# EEM_Connectors_JTAG.net
KiCad netlist of a schematic drawn in Altium Designer
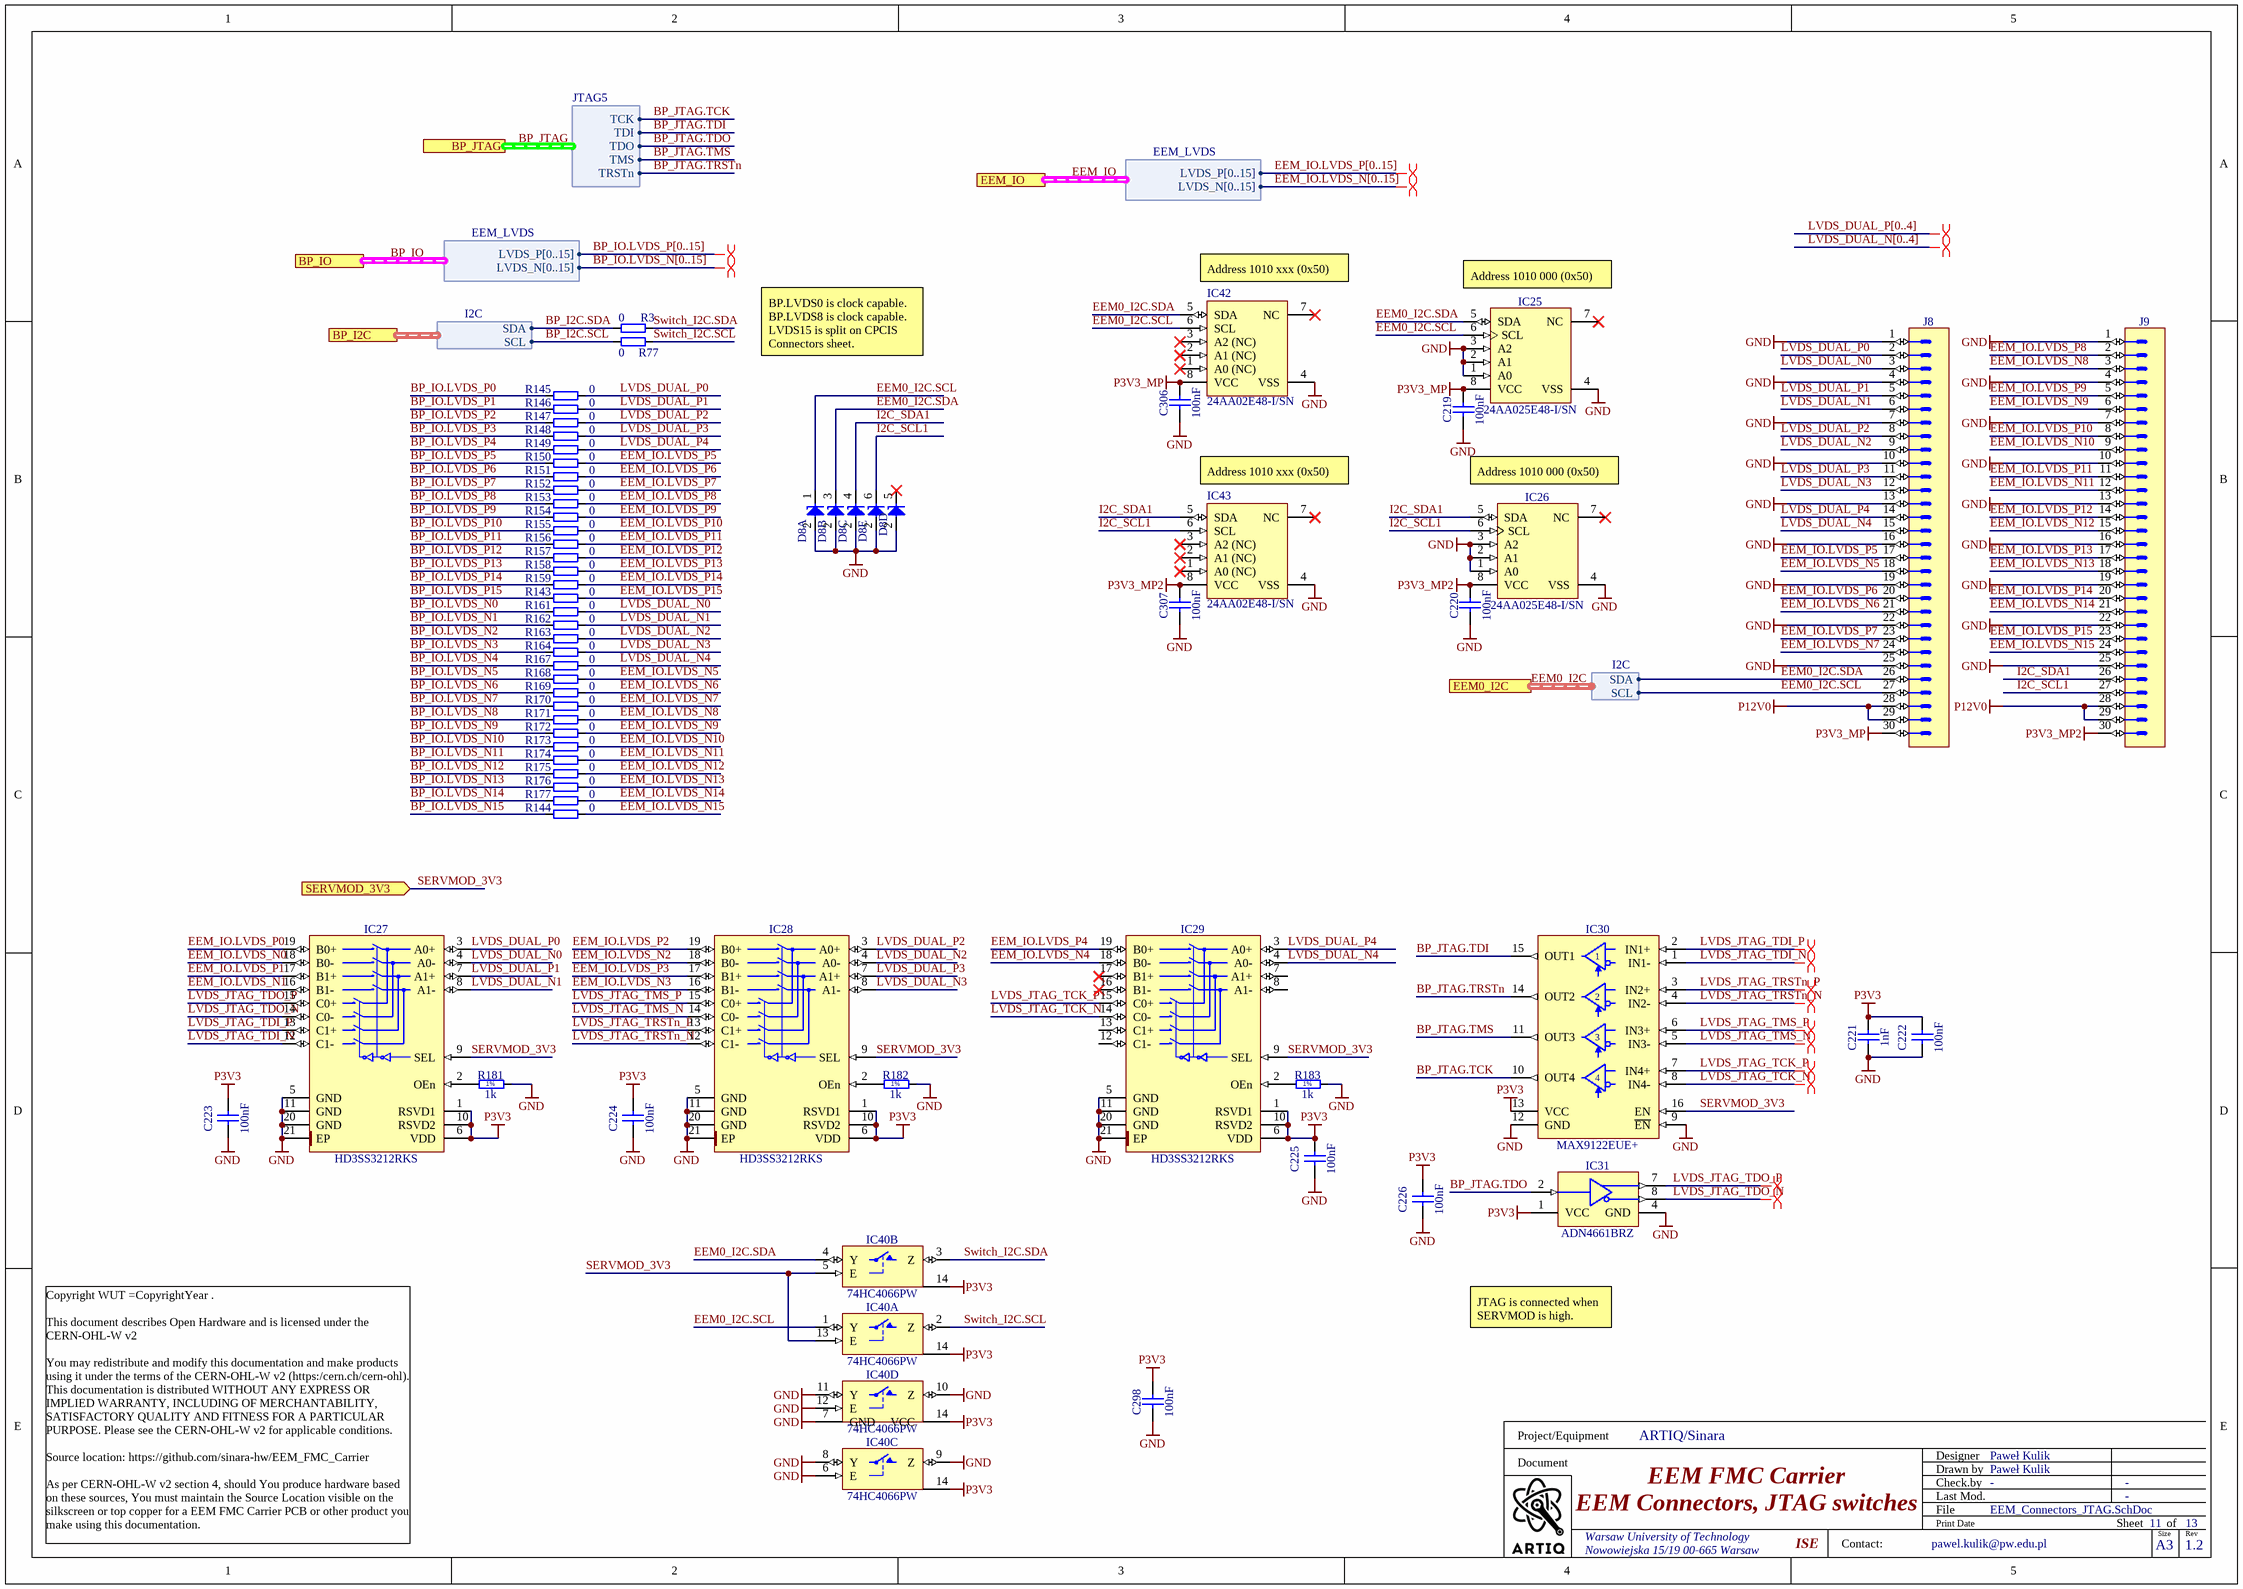
[diagram p0: EEM_Connectors_JTAG.SchDoc]

(export (version "E")
  (design (tool "Eeschema 10.0.6"))
  (components
    (comp (ref "C219")
      (value "100nF")
      (footprint "CAPC1005X55N")
      (description "Non-polarised capacitor")
      (fields
        (field (name "PART NUMBER") "CC0402_100NF_25V_10%_X7R_YUDEN_TMK105B7104KVHF")
        (field (name "VOLTAGE") "25V")
        (field (name "AUTHOR") "CERN DEM JLC")
      )
      (libsource (lib "Capacitors") (part "Capacitor - non polarized"))
    )
    (comp (ref "C220")
      (value "100nF")
      (footprint "CAPC1005X55N")
      (description "Non-polarised capacitor")
      (fields
        (field (name "PART NUMBER") "CC0402_100NF_16V_10%_X5R")
        (field (name "VOLTAGE") "16V")
        (field (name "AUTHOR") "CERN DEM JLC")
      )
      (libsource (lib "Capacitors") (part "Capacitor - non polarized"))
    )
    (comp (ref "C221")
      (value "1nF")
      (footprint "CAPC1005X55N")
      (description "Non-polarised capacitor")
      (fields
        (field (name "MANUFACTURER PART NUMBER") "CC0402_1NF_50V_10%_X7R")
        (field (name "MANUFACTURER") "GENERIC")
        (field (name "AUTHOR") "CERN DEM JLC")
      )
      (libsource (lib "Capacitors") (part "Capacitor - non polarized"))
    )
    (comp (ref "C222")
      (value "100nF")
      (footprint "CAPC1005X55N")
      (description "Non-polarised capacitor")
      (fields
        (field (name "PART NUMBER") "CC0402_100NF_25V_10%_X7R_YUDEN_TMK105B7104KVHF")
        (field (name "VOLTAGE") "25V")
        (field (name "AUTHOR") "CERN DEM JLC")
      )
      (libsource (lib "Capacitors") (part "Capacitor - non polarized"))
    )
    (comp (ref "C223")
      (value "100nF")
      (footprint "CAPC1005X55N")
      (description "Non-polarised capacitor")
      (fields
        (field (name "PART NUMBER") "CC0402_100NF_25V_10%_X7R_YUDEN_TMK105B7104KVHF")
        (field (name "VOLTAGE") "25V")
        (field (name "AUTHOR") "CERN DEM JLC")
      )
      (libsource (lib "Capacitors") (part "Capacitor - non polarized"))
    )
    (comp (ref "C224")
      (value "100nF")
      (footprint "CAPC1005X55N")
      (description "Non-polarised capacitor")
      (fields
        (field (name "PART NUMBER") "CC0402_100NF_25V_10%_X7R_YUDEN_TMK105B7104KVHF")
        (field (name "VOLTAGE") "25V")
        (field (name "AUTHOR") "CERN DEM JLC")
      )
      (libsource (lib "Capacitors") (part "Capacitor - non polarized"))
    )
    (comp (ref "C225")
      (value "100nF")
      (footprint "CAPC1005X55N")
      (description "Non-polarised capacitor")
      (fields
        (field (name "PART NUMBER") "CC0402_100NF_25V_10%_X7R_YUDEN_TMK105B7104KVHF")
        (field (name "VOLTAGE") "25V")
        (field (name "AUTHOR") "CERN DEM JLC")
      )
      (libsource (lib "Capacitors") (part "Capacitor - non polarized"))
    )
    (comp (ref "C226")
      (value "100nF")
      (footprint "CAPC1005X55N")
      (description "Non-polarised capacitor")
      (fields
        (field (name "PART NUMBER") "CC0402_100NF_25V_10%_X7R_YUDEN_TMK105B7104KVHF")
        (field (name "VOLTAGE") "25V")
        (field (name "AUTHOR") "CERN DEM JLC")
      )
      (libsource (lib "Capacitors") (part "Capacitor - non polarized"))
    )
    (comp (ref "C298")
      (value "100nF")
      (footprint "CAPC1005X55N")
      (description "Non-polarised capacitor")
      (fields
        (field (name "PART NUMBER") "CC0402_100NF_16V_10%_X5R")
        (field (name "VOLTAGE") "16V")
        (field (name "AUTHOR") "CERN DEM JLC")
      )
      (libsource (lib "Capacitors") (part "Capacitor - non polarized"))
    )
    (comp (ref "C306")
      (value "100nF")
      (footprint "CAPC1005X55N")
      (description "Non-polarised capacitor")
      (fields
        (field (name "PART NUMBER") "CC0402_100NF_25V_10%_X7R_YUDEN_TMK105B7104KVHF")
        (field (name "VOLTAGE") "25V")
        (field (name "AUTHOR") "CERN DEM JLC")
      )
      (libsource (lib "Capacitors") (part "Capacitor - non polarized"))
    )
    (comp (ref "C307")
      (value "100nF")
      (footprint "CAPC1005X55N")
      (description "Non-polarised capacitor")
      (fields
        (field (name "PART NUMBER") "CC0402_100NF_25V_10%_X7R_YUDEN_TMK105B7104KVHF")
        (field (name "VOLTAGE") "25V")
        (field (name "AUTHOR") "CERN DEM JLC")
      )
      (libsource (lib "Capacitors") (part "Capacitor - non polarized"))
    )
    (comp (ref "D8")
      (value "PESD3V3L5UY")
      (footprint "SOT65P210X110-6N")
      (description "Fivefold ESD Protection Diode Arrays")
      (fields
        (field (name "VOLTAGE") "3.3V")
        (field (name "POWER") "200W")
        (field (name "AUTHOR") "CERN DEM WB")
      )
      (libsource (lib "ICs And Semiconductors") (part "PESD Array 5diodes 6pins Common anode2"))
    )
    (comp (ref "IC25")
      (value "24AA025E48-I/SN")
      (footprint "SOIC127P600X175-8N")
      (description "1.7V-5.5V, 2K I2C™ Serial EEPROMs with EUI-48™ Node Identity")
      (fields (field (name "MANUFACTURER") "MICROCHIP TECHNOLOGY") (field (name "AUTHOR") "CERN DEM MR"))
      (libsource (lib "ICs And Semiconductors") (part "24AA025E48-I/SN"))
    )
    (comp (ref "IC26")
      (value "24AA025E48-I/SN")
      (footprint "SOIC127P600X175-8N")
      (description "1.7V-5.5V, 2K I2C™ Serial EEPROMs with EUI-48™ Node Identity")
      (fields (field (name "MANUFACTURER") "MICROCHIP TECHNOLOGY") (field (name "AUTHOR") "CERN DEM MR"))
      (libsource (lib "ICs And Semiconductors") (part "24AA025E48-I/SN"))
    )
    (comp (ref "IC27")
      (value "HD3SS3212RKS")
      (footprint "TEXAS_RKS0020A")
      (description "Two-Channel Differential 2:1/1:2 USB3.1 Mux/Demux")
      (fields (field (name "MANUFACTURER") "TEXAS INSTRUMENTS") (field (name "AUTHOR") "CERN DEM BC"))
      (libsource (lib "ICs And Semiconductors") (part "HD3SS3212RKS"))
    )
    (comp (ref "IC28")
      (value "HD3SS3212RKS")
      (footprint "TEXAS_RKS0020A")
      (description "Two-Channel Differential 2:1/1:2 USB3.1 Mux/Demux")
      (fields (field (name "MANUFACTURER") "TEXAS INSTRUMENTS") (field (name "AUTHOR") "CERN DEM BC"))
      (libsource (lib "ICs And Semiconductors") (part "HD3SS3212RKS"))
    )
    (comp (ref "IC29")
      (value "HD3SS3212RKS")
      (footprint "TEXAS_RKS0020A")
      (description "Two-Channel Differential 2:1/1:2 USB3.1 Mux/Demux")
      (fields (field (name "MANUFACTURER") "TEXAS INSTRUMENTS") (field (name "AUTHOR") "CERN DEM BC"))
      (libsource (lib "ICs And Semiconductors") (part "HD3SS3212RKS"))
    )
    (comp (ref "IC30")
      (value "MAX9122EUE+")
      (footprint "SOP65P640X110-16N")
      (description "Quad LVDS Line Receivers with Integrated Termination and Flow-Through Pinout")
      (fields (field (name "MANUFACTURER") "MAXIM") (field (name "AUTHOR") "CERN DEM MR"))
      (libsource (lib "ICs And Semiconductors") (part "MAX9122"))
    )
    (comp (ref "IC31")
      (value "ADN4661BRZ")
      (footprint "SOIC127P600X175-8N")
      (description "Single, 3V, CMOS, LVDS, High Speed Differential Driver")
      (fields (field (name "MANUFACTURER") "ANALOG DEVICES") (field (name "AUTHOR") "CERN DEM JMW"))
      (libsource (lib "ICs And Semiconductors") (part "ADN4661"))
    )
    (comp (ref "IC40")
      (value "74HC4066PW")
      (footprint "SOP65P640X110-14N")
      (fields (field (name "MANUFACTURER") "NXP SEMICONDUCTORS") (field (name "AUTHOR") "CERN DEM JLC"))
      (libsource (lib "ICs And Semiconductors") (part "4066"))
    )
    (comp (ref "IC42")
      (value "24AA02E48-I/SN")
      (footprint "SOIC127")
      (description "1.7V-5.5V, 2K I2C™ Serial EEPROMs with EUI-48™ Node Identity")
      (libsource (lib "Integrated_Library_MP") (part "24AA02E48-I/SN"))
    )
    (comp (ref "IC43")
      (value "24AA02E48-I/SN")
      (footprint "SOIC127")
      (description "1.7V-5.5V, 2K I2C™ Serial EEPROMs with EUI-48™ Node Identity")
      (libsource (lib "Integrated_Library_MP") (part "24AA02E48-I/SN"))
    )
    (comp (ref "J8")
      (value "~")
      (footprint "3M_N2530-6002RB")
      (description "Connector 30 Male")
      (fields
        (field (name "PART NUMBER") "3M_N2530-6002RB")
        (field (name "MANUFACTURER") "3M")
        (field (name "AUTHOR") "CERN DEM JLC")
      )
      (libsource (lib "Connectors") (part "Connector 30 Male"))
    )
    (comp (ref "J9")
      (value "~")
      (footprint "3M_N2530-6002RB")
      (description "Connector 30 Male")
      (fields
        (field (name "PART NUMBER") "3M_N2530-6002RB")
        (field (name "MANUFACTURER") "3M")
        (field (name "AUTHOR") "CERN DEM JLC")
      )
      (libsource (lib "Connectors") (part "Connector 30 Male"))
    )
    (comp (ref "R3")
      (value "0")
      (footprint "RESC1005X40N")
      (description "Resistor")
      (fields
        (field (name "PART NUMBER") "R0402_0R_JUMPER")
        (field (name "MANUFACTURER") "GENERIC")
        (field (name "AUTHOR") "CERN DEM JLC")
      )
      (libsource (lib "Resistors") (part "Resistor"))
    )
    (comp (ref "R77")
      (value "0")
      (footprint "RESC1005X40N")
      (description "Resistor")
      (fields
        (field (name "PART NUMBER") "R0402_0R_JUMPER")
        (field (name "MANUFACTURER") "GENERIC")
        (field (name "AUTHOR") "CERN DEM JLC")
      )
      (libsource (lib "Resistors") (part "Resistor"))
    )
    (comp (ref "R143")
      (value "0")
      (footprint "RESC0603X28N")
      (description "Resistor")
      (fields
        (field (name "PART NUMBER") "R0201_0R_JUMPER")
        (field (name "MANUFACTURER") "GENERIC")
        (field (name "AUTHOR") "CERN DEM JLC")
      )
      (libsource (lib "Resistors") (part "Resistor"))
    )
    (comp (ref "R144")
      (value "0")
      (footprint "RESC0603X28N")
      (description "Resistor")
      (fields
        (field (name "PART NUMBER") "R0201_0R_JUMPER")
        (field (name "MANUFACTURER") "GENERIC")
        (field (name "AUTHOR") "CERN DEM JLC")
      )
      (libsource (lib "Resistors") (part "Resistor"))
    )
    (comp (ref "R145")
      (value "0")
      (footprint "RESC1005X40N")
      (description "Resistor")
      (fields
        (field (name "PART NUMBER") "R0402_0R_JUMPER")
        (field (name "MANUFACTURER") "GENERIC")
        (field (name "AUTHOR") "CERN DEM JLC")
      )
      (libsource (lib "Resistors") (part "Resistor"))
    )
    (comp (ref "R146")
      (value "0")
      (footprint "RESC1005X40N")
      (description "Resistor")
      (fields
        (field (name "PART NUMBER") "R0402_0R_JUMPER")
        (field (name "MANUFACTURER") "GENERIC")
        (field (name "AUTHOR") "CERN DEM JLC")
      )
      (libsource (lib "Resistors") (part "Resistor"))
    )
    (comp (ref "R147")
      (value "0")
      (footprint "RESC1005X40N")
      (description "Resistor")
      (fields
        (field (name "PART NUMBER") "R0402_0R_JUMPER")
        (field (name "MANUFACTURER") "GENERIC")
        (field (name "AUTHOR") "CERN DEM JLC")
      )
      (libsource (lib "Resistors") (part "Resistor"))
    )
    (comp (ref "R148")
      (value "0")
      (footprint "RESC1005X40N")
      (description "Resistor")
      (fields
        (field (name "PART NUMBER") "R0402_0R_JUMPER")
        (field (name "MANUFACTURER") "GENERIC")
        (field (name "AUTHOR") "CERN DEM JLC")
      )
      (libsource (lib "Resistors") (part "Resistor"))
    )
    (comp (ref "R149")
      (value "0")
      (footprint "RESC1005X40N")
      (description "Resistor")
      (fields
        (field (name "PART NUMBER") "R0402_0R_JUMPER")
        (field (name "MANUFACTURER") "GENERIC")
        (field (name "AUTHOR") "CERN DEM JLC")
      )
      (libsource (lib "Resistors") (part "Resistor"))
    )
    (comp (ref "R150")
      (value "0")
      (footprint "RESC1005X40N")
      (description "Resistor")
      (fields
        (field (name "PART NUMBER") "R0402_0R_JUMPER")
        (field (name "MANUFACTURER") "GENERIC")
        (field (name "AUTHOR") "CERN DEM JLC")
      )
      (libsource (lib "Resistors") (part "Resistor"))
    )
    (comp (ref "R151")
      (value "0")
      (footprint "RESC1005X40N")
      (description "Resistor")
      (fields
        (field (name "PART NUMBER") "R0402_0R_JUMPER")
        (field (name "MANUFACTURER") "GENERIC")
        (field (name "AUTHOR") "CERN DEM JLC")
      )
      (libsource (lib "Resistors") (part "Resistor"))
    )
    (comp (ref "R152")
      (value "0")
      (footprint "RESC1005X40N")
      (description "Resistor")
      (fields
        (field (name "PART NUMBER") "R0402_0R_JUMPER")
        (field (name "MANUFACTURER") "GENERIC")
        (field (name "AUTHOR") "CERN DEM JLC")
      )
      (libsource (lib "Resistors") (part "Resistor"))
    )
    (comp (ref "R153")
      (value "0")
      (footprint "RESC1005X40N")
      (description "Resistor")
      (fields
        (field (name "PART NUMBER") "R0402_0R_JUMPER")
        (field (name "MANUFACTURER") "GENERIC")
        (field (name "AUTHOR") "CERN DEM JLC")
      )
      (libsource (lib "Resistors") (part "Resistor"))
    )
    (comp (ref "R154")
      (value "0")
      (footprint "RESC1005X40N")
      (description "Resistor")
      (fields
        (field (name "PART NUMBER") "R0402_0R_JUMPER")
        (field (name "MANUFACTURER") "GENERIC")
        (field (name "AUTHOR") "CERN DEM JLC")
      )
      (libsource (lib "Resistors") (part "Resistor"))
    )
    (comp (ref "R155")
      (value "0")
      (footprint "RESC1005X40N")
      (description "Resistor")
      (fields
        (field (name "PART NUMBER") "R0402_0R_JUMPER")
        (field (name "MANUFACTURER") "GENERIC")
        (field (name "AUTHOR") "CERN DEM JLC")
      )
      (libsource (lib "Resistors") (part "Resistor"))
    )
    (comp (ref "R156")
      (value "0")
      (footprint "RESC1005X40N")
      (description "Resistor")
      (fields
        (field (name "PART NUMBER") "R0402_0R_JUMPER")
        (field (name "MANUFACTURER") "GENERIC")
        (field (name "AUTHOR") "CERN DEM JLC")
      )
      (libsource (lib "Resistors") (part "Resistor"))
    )
    (comp (ref "R157")
      (value "0")
      (footprint "RESC1005X40N")
      (description "Resistor")
      (fields
        (field (name "PART NUMBER") "R0402_0R_JUMPER")
        (field (name "MANUFACTURER") "GENERIC")
        (field (name "AUTHOR") "CERN DEM JLC")
      )
      (libsource (lib "Resistors") (part "Resistor"))
    )
    (comp (ref "R158")
      (value "0")
      (footprint "RESC1005X40N")
      (description "Resistor")
      (fields
        (field (name "PART NUMBER") "R0402_0R_JUMPER")
        (field (name "MANUFACTURER") "GENERIC")
        (field (name "AUTHOR") "CERN DEM JLC")
      )
      (libsource (lib "Resistors") (part "Resistor"))
    )
    (comp (ref "R159")
      (value "0")
      (footprint "RESC1005X40N")
      (description "Resistor")
      (fields
        (field (name "PART NUMBER") "R0402_0R_JUMPER")
        (field (name "MANUFACTURER") "GENERIC")
        (field (name "AUTHOR") "CERN DEM JLC")
      )
      (libsource (lib "Resistors") (part "Resistor"))
    )
    (comp (ref "R161")
      (value "0")
      (footprint "RESC1005X40N")
      (description "Resistor")
      (fields
        (field (name "PART NUMBER") "R0402_0R_JUMPER")
        (field (name "MANUFACTURER") "GENERIC")
        (field (name "AUTHOR") "CERN DEM JLC")
      )
      (libsource (lib "Resistors") (part "Resistor"))
    )
    (comp (ref "R162")
      (value "0")
      (footprint "RESC1005X40N")
      (description "Resistor")
      (fields
        (field (name "PART NUMBER") "R0402_0R_JUMPER")
        (field (name "MANUFACTURER") "GENERIC")
        (field (name "AUTHOR") "CERN DEM JLC")
      )
      (libsource (lib "Resistors") (part "Resistor"))
    )
    (comp (ref "R163")
      (value "0")
      (footprint "RESC1005X40N")
      (description "Resistor")
      (fields
        (field (name "PART NUMBER") "R0402_0R_JUMPER")
        (field (name "MANUFACTURER") "GENERIC")
        (field (name "AUTHOR") "CERN DEM JLC")
      )
      (libsource (lib "Resistors") (part "Resistor"))
    )
    (comp (ref "R164")
      (value "0")
      (footprint "RESC1005X40N")
      (description "Resistor")
      (fields
        (field (name "PART NUMBER") "R0402_0R_JUMPER")
        (field (name "MANUFACTURER") "GENERIC")
        (field (name "AUTHOR") "CERN DEM JLC")
      )
      (libsource (lib "Resistors") (part "Resistor"))
    )
    (comp (ref "R167")
      (value "0")
      (footprint "RESC1005X40N")
      (description "Resistor")
      (fields
        (field (name "PART NUMBER") "R0402_0R_JUMPER")
        (field (name "MANUFACTURER") "GENERIC")
        (field (name "AUTHOR") "CERN DEM JLC")
      )
      (libsource (lib "Resistors") (part "Resistor"))
    )
    (comp (ref "R168")
      (value "0")
      (footprint "RESC1005X40N")
      (description "Resistor")
      (fields
        (field (name "PART NUMBER") "R0402_0R_JUMPER")
        (field (name "MANUFACTURER") "GENERIC")
        (field (name "AUTHOR") "CERN DEM JLC")
      )
      (libsource (lib "Resistors") (part "Resistor"))
    )
    (comp (ref "R169")
      (value "0")
      (footprint "RESC1005X40N")
      (description "Resistor")
      (fields
        (field (name "PART NUMBER") "R0402_0R_JUMPER")
        (field (name "MANUFACTURER") "GENERIC")
        (field (name "AUTHOR") "CERN DEM JLC")
      )
      (libsource (lib "Resistors") (part "Resistor"))
    )
    (comp (ref "R170")
      (value "0")
      (footprint "RESC1005X40N")
      (description "Resistor")
      (fields
        (field (name "PART NUMBER") "R0402_0R_JUMPER")
        (field (name "MANUFACTURER") "GENERIC")
        (field (name "AUTHOR") "CERN DEM JLC")
      )
      (libsource (lib "Resistors") (part "Resistor"))
    )
    (comp (ref "R171")
      (value "0")
      (footprint "RESC1005X40N")
      (description "Resistor")
      (fields
        (field (name "PART NUMBER") "R0402_0R_JUMPER")
        (field (name "MANUFACTURER") "GENERIC")
        (field (name "AUTHOR") "CERN DEM JLC")
      )
      (libsource (lib "Resistors") (part "Resistor"))
    )
    (comp (ref "R172")
      (value "0")
      (footprint "RESC1005X40N")
      (description "Resistor")
      (fields
        (field (name "PART NUMBER") "R0402_0R_JUMPER")
        (field (name "MANUFACTURER") "GENERIC")
        (field (name "AUTHOR") "CERN DEM JLC")
      )
      (libsource (lib "Resistors") (part "Resistor"))
    )
    (comp (ref "R173")
      (value "0")
      (footprint "RESC1005X40N")
      (description "Resistor")
      (fields
        (field (name "PART NUMBER") "R0402_0R_JUMPER")
        (field (name "MANUFACTURER") "GENERIC")
        (field (name "AUTHOR") "CERN DEM JLC")
      )
      (libsource (lib "Resistors") (part "Resistor"))
    )
    (comp (ref "R174")
      (value "0")
      (footprint "RESC1005X40N")
      (description "Resistor")
      (fields
        (field (name "PART NUMBER") "R0402_0R_JUMPER")
        (field (name "MANUFACTURER") "GENERIC")
        (field (name "AUTHOR") "CERN DEM JLC")
      )
      (libsource (lib "Resistors") (part "Resistor"))
    )
    (comp (ref "R175")
      (value "0")
      (footprint "RESC1005X40N")
      (description "Resistor")
      (fields
        (field (name "PART NUMBER") "R0402_0R_JUMPER")
        (field (name "MANUFACTURER") "GENERIC")
        (field (name "AUTHOR") "CERN DEM JLC")
      )
      (libsource (lib "Resistors") (part "Resistor"))
    )
    (comp (ref "R176")
      (value "0")
      (footprint "RESC1005X40N")
      (description "Resistor")
      (fields
        (field (name "PART NUMBER") "R0402_0R_JUMPER")
        (field (name "MANUFACTURER") "GENERIC")
        (field (name "AUTHOR") "CERN DEM JLC")
      )
      (libsource (lib "Resistors") (part "Resistor"))
    )
    (comp (ref "R177")
      (value "0")
      (footprint "RESC1005X40N")
      (description "Resistor")
      (fields
        (field (name "PART NUMBER") "R0402_0R_JUMPER")
        (field (name "MANUFACTURER") "GENERIC")
        (field (name "AUTHOR") "CERN DEM JLC")
      )
      (libsource (lib "Resistors") (part "Resistor"))
    )
    (comp (ref "R181")
      (value "1k")
      (footprint "RESC1005X40N")
      (description "Resistor - 1%")
      (fields
        (field (name "PART NUMBER") "R0402_1K_1%_0.0625W_100PPM")
        (field (name "POWER") "0.0625W")
        (field (name "AUTHOR") "CERN DEM JLC")
      )
      (libsource (lib "Resistors") (part "Resistor - 1%"))
    )
    (comp (ref "R182")
      (value "1k")
      (footprint "RESC1005X40N")
      (description "Resistor - 1%")
      (fields
        (field (name "PART NUMBER") "R0402_1K_1%_0.0625W_100PPM")
        (field (name "POWER") "0.0625W")
        (field (name "AUTHOR") "CERN DEM JLC")
      )
      (libsource (lib "Resistors") (part "Resistor - 1%"))
    )
    (comp (ref "R183")
      (value "1k")
      (footprint "RESC1005X40N")
      (description "Resistor - 1%")
      (fields
        (field (name "PART NUMBER") "R0402_1K_1%_0.0625W_100PPM")
        (field (name "POWER") "0.0625W")
        (field (name "AUTHOR") "CERN DEM JLC")
      )
      (libsource (lib "Resistors") (part "Resistor - 1%"))
    )
  )
  (nets
    (net (code "6") (name "/BP_I2C.SCL") (class "Default")
      (node (ref "R77") (pin "1") (pinfunction "1_1") (pintype "passive"))
    )
    (net (code "7") (name "/BP_I2C.SDA") (class "Default")
      (node (ref "R3") (pin "1") (pinfunction "1_1") (pintype "passive"))
    )
    (net (code "8") (name "/BP_IO.LVDS_N0") (class "Default")
      (node (ref "R161") (pin "1") (pinfunction "1_1") (pintype "passive"))
    )
    (net (code "9") (name "/BP_IO.LVDS_N1") (class "Default")
      (node (ref "R162") (pin "1") (pinfunction "1_1") (pintype "passive"))
    )
    (net (code "10") (name "/BP_IO.LVDS_N2") (class "Default")
      (node (ref "R163") (pin "1") (pinfunction "1_1") (pintype "passive"))
    )
    (net (code "11") (name "/BP_IO.LVDS_N3") (class "Default")
      (node (ref "R164") (pin "1") (pinfunction "1_1") (pintype "passive"))
    )
    (net (code "12") (name "/BP_IO.LVDS_N4") (class "Default")
      (node (ref "R167") (pin "1") (pinfunction "1_1") (pintype "passive"))
    )
    (net (code "13") (name "/BP_IO.LVDS_N5") (class "Default")
      (node (ref "R168") (pin "1") (pinfunction "1_1") (pintype "passive"))
    )
    (net (code "14") (name "/BP_IO.LVDS_N6") (class "Default")
      (node (ref "R169") (pin "1") (pinfunction "1_1") (pintype "passive"))
    )
    (net (code "15") (name "/BP_IO.LVDS_N7") (class "Default")
      (node (ref "R170") (pin "1") (pinfunction "1_1") (pintype "passive"))
    )
    (net (code "16") (name "/BP_IO.LVDS_N8") (class "Default")
      (node (ref "R171") (pin "1") (pinfunction "1_1") (pintype "passive"))
    )
    (net (code "17") (name "/BP_IO.LVDS_N9") (class "Default")
      (node (ref "R172") (pin "1") (pinfunction "1_1") (pintype "passive"))
    )
    (net (code "18") (name "/BP_IO.LVDS_N10") (class "Default")
      (node (ref "R173") (pin "1") (pinfunction "1_1") (pintype "passive"))
    )
    (net (code "19") (name "/BP_IO.LVDS_N11") (class "Default")
      (node (ref "R174") (pin "1") (pinfunction "1_1") (pintype "passive"))
    )
    (net (code "20") (name "/BP_IO.LVDS_N12") (class "Default")
      (node (ref "R175") (pin "1") (pinfunction "1_1") (pintype "passive"))
    )
    (net (code "21") (name "/BP_IO.LVDS_N13") (class "Default")
      (node (ref "R176") (pin "1") (pinfunction "1_1") (pintype "passive"))
    )
    (net (code "22") (name "/BP_IO.LVDS_N14") (class "Default")
      (node (ref "R177") (pin "1") (pinfunction "1_1") (pintype "passive"))
    )
    (net (code "23") (name "/BP_IO.LVDS_N15") (class "Default")
      (node (ref "R144") (pin "2") (pinfunction "2_2") (pintype "passive"))
    )
    (net (code "24") (name "/BP_IO.LVDS_P0") (class "Default")
      (node (ref "R145") (pin "1") (pinfunction "1_1") (pintype "passive"))
    )
    (net (code "25") (name "/BP_IO.LVDS_P1") (class "Default")
      (node (ref "R146") (pin "1") (pinfunction "1_1") (pintype "passive"))
    )
    (net (code "26") (name "/BP_IO.LVDS_P2") (class "Default")
      (node (ref "R147") (pin "1") (pinfunction "1_1") (pintype "passive"))
    )
    (net (code "27") (name "/BP_IO.LVDS_P3") (class "Default")
      (node (ref "R148") (pin "1") (pinfunction "1_1") (pintype "passive"))
    )
    (net (code "28") (name "/BP_IO.LVDS_P4") (class "Default")
      (node (ref "R149") (pin "1") (pinfunction "1_1") (pintype "passive"))
    )
    (net (code "29") (name "/BP_IO.LVDS_P5") (class "Default")
      (node (ref "R150") (pin "1") (pinfunction "1_1") (pintype "passive"))
    )
    (net (code "30") (name "/BP_IO.LVDS_P6") (class "Default")
      (node (ref "R151") (pin "1") (pinfunction "1_1") (pintype "passive"))
    )
    (net (code "31") (name "/BP_IO.LVDS_P7") (class "Default")
      (node (ref "R152") (pin "1") (pinfunction "1_1") (pintype "passive"))
    )
    (net (code "32") (name "/BP_IO.LVDS_P8") (class "Default")
      (node (ref "R153") (pin "1") (pinfunction "1_1") (pintype "passive"))
    )
    (net (code "33") (name "/BP_IO.LVDS_P9") (class "Default")
      (node (ref "R154") (pin "1") (pinfunction "1_1") (pintype "passive"))
    )
    (net (code "34") (name "/BP_IO.LVDS_P10") (class "Default")
      (node (ref "R155") (pin "1") (pinfunction "1_1") (pintype "passive"))
    )
    (net (code "35") (name "/BP_IO.LVDS_P11") (class "Default")
      (node (ref "R156") (pin "1") (pinfunction "1_1") (pintype "passive"))
    )
    (net (code "36") (name "/BP_IO.LVDS_P12") (class "Default")
      (node (ref "R157") (pin "1") (pinfunction "1_1") (pintype "passive"))
    )
    (net (code "37") (name "/BP_IO.LVDS_P13") (class "Default")
      (node (ref "R158") (pin "1") (pinfunction "1_1") (pintype "passive"))
    )
    (net (code "38") (name "/BP_IO.LVDS_P14") (class "Default")
      (node (ref "R159") (pin "1") (pinfunction "1_1") (pintype "passive"))
    )
    (net (code "39") (name "/BP_IO.LVDS_P15") (class "Default")
      (node (ref "R143") (pin "2") (pinfunction "2_2") (pintype "passive"))
    )
    (net (code "41") (name "/BP_JTAG.TCK") (class "Default")
      (node (ref "IC30") (pin "10") (pinfunction "OUT4_10") (pintype "output"))
    )
    (net (code "42") (name "/BP_JTAG.TDI") (class "Default")
      (node (ref "IC30") (pin "15") (pinfunction "OUT1_15") (pintype "output"))
    )
    (net (code "43") (name "/BP_JTAG.TDO") (class "Default")
      (node (ref "IC31") (pin "2") (pinfunction "DIN_2") (pintype "input"))
    )
    (net (code "44") (name "/BP_JTAG.TMS") (class "Default")
      (node (ref "IC30") (pin "11") (pinfunction "OUT3_11") (pintype "output"))
    )
    (net (code "45") (name "/BP_JTAG.TRSTn") (class "Default")
      (node (ref "IC30") (pin "14") (pinfunction "OUT2_14") (pintype "output"))
    )
    (net (code "47") (name "/EEM0_I2C.SCL") (class "Default")
      (node (ref "D8") (pin "1") (pinfunction "C_1") (pintype "passive"))
      (node (ref "IC25") (pin "6") (pinfunction "SCL_6") (pintype "input"))
      (node (ref "IC40") (pin "1") (pinfunction "Y_1") (pintype "bidirectional"))
      (node (ref "IC42") (pin "6") (pinfunction "SCL_6") (pintype "input"))
      (node (ref "J8") (pin "27") (pinfunction "27_27") (pintype "bidirectional"))
    )
    (net (code "48") (name "/EEM0_I2C.SDA") (class "Default")
      (node (ref "D8") (pin "3") (pinfunction "C_3") (pintype "passive"))
      (node (ref "IC25") (pin "5") (pinfunction "SDA_5") (pintype "bidirectional"))
      (node (ref "IC40") (pin "4") (pinfunction "Y_4") (pintype "bidirectional"))
      (node (ref "IC42") (pin "5") (pinfunction "SDA_5") (pintype "bidirectional"))
      (node (ref "J8") (pin "26") (pinfunction "26_26") (pintype "bidirectional"))
    )
    (net (code "50") (name "/EEM_IO.LVDS_N0") (class "Default")
      (node (ref "IC27") (pin "18") (pinfunction "B0-_18") (pintype "bidirectional"))
    )
    (net (code "51") (name "/EEM_IO.LVDS_N1") (class "Default")
      (node (ref "IC27") (pin "16") (pinfunction "B1-_16") (pintype "bidirectional"))
    )
    (net (code "52") (name "/EEM_IO.LVDS_N2") (class "Default")
      (node (ref "IC28") (pin "18") (pinfunction "B0-_18") (pintype "bidirectional"))
    )
    (net (code "53") (name "/EEM_IO.LVDS_N3") (class "Default")
      (node (ref "IC28") (pin "16") (pinfunction "B1-_16") (pintype "bidirectional"))
    )
    (net (code "54") (name "/EEM_IO.LVDS_N4") (class "Default")
      (node (ref "IC29") (pin "18") (pinfunction "B0-_18") (pintype "bidirectional"))
    )
    (net (code "55") (name "/EEM_IO.LVDS_N5") (class "Default")
      (node (ref "J8") (pin "18") (pinfunction "18_18") (pintype "bidirectional"))
      (node (ref "R168") (pin "2") (pinfunction "2_2") (pintype "passive"))
    )
    (net (code "56") (name "/EEM_IO.LVDS_N6") (class "Default")
      (node (ref "J8") (pin "21") (pinfunction "21_21") (pintype "bidirectional"))
      (node (ref "R169") (pin "2") (pinfunction "2_2") (pintype "passive"))
    )
    (net (code "57") (name "/EEM_IO.LVDS_N7") (class "Default")
      (node (ref "J8") (pin "24") (pinfunction "24_24") (pintype "bidirectional"))
      (node (ref "R170") (pin "2") (pinfunction "2_2") (pintype "passive"))
    )
    (net (code "58") (name "/EEM_IO.LVDS_N8") (class "Default")
      (node (ref "J9") (pin "3") (pinfunction "3_3") (pintype "bidirectional"))
      (node (ref "R171") (pin "2") (pinfunction "2_2") (pintype "passive"))
    )
    (net (code "59") (name "/EEM_IO.LVDS_N9") (class "Default")
      (node (ref "J9") (pin "6") (pinfunction "6_6") (pintype "bidirectional"))
      (node (ref "R172") (pin "2") (pinfunction "2_2") (pintype "passive"))
    )
    (net (code "60") (name "/EEM_IO.LVDS_N10") (class "Default")
      (node (ref "J9") (pin "9") (pinfunction "9_9") (pintype "bidirectional"))
      (node (ref "R173") (pin "2") (pinfunction "2_2") (pintype "passive"))
    )
    (net (code "61") (name "/EEM_IO.LVDS_N11") (class "Default")
      (node (ref "J9") (pin "12") (pinfunction "12_12") (pintype "bidirectional"))
      (node (ref "R174") (pin "2") (pinfunction "2_2") (pintype "passive"))
    )
    (net (code "62") (name "/EEM_IO.LVDS_N12") (class "Default")
      (node (ref "J9") (pin "15") (pinfunction "15_15") (pintype "bidirectional"))
      (node (ref "R175") (pin "2") (pinfunction "2_2") (pintype "passive"))
    )
    (net (code "63") (name "/EEM_IO.LVDS_N13") (class "Default")
      (node (ref "J9") (pin "18") (pinfunction "18_18") (pintype "bidirectional"))
      (node (ref "R176") (pin "2") (pinfunction "2_2") (pintype "passive"))
    )
    (net (code "64") (name "/EEM_IO.LVDS_N14") (class "Default")
      (node (ref "J9") (pin "21") (pinfunction "21_21") (pintype "bidirectional"))
      (node (ref "R177") (pin "2") (pinfunction "2_2") (pintype "passive"))
    )
    (net (code "65") (name "/EEM_IO.LVDS_N15") (class "Default")
      (node (ref "J9") (pin "24") (pinfunction "24_24") (pintype "bidirectional"))
      (node (ref "R144") (pin "1") (pinfunction "1_1") (pintype "passive"))
    )
    (net (code "66") (name "/EEM_IO.LVDS_P0") (class "Default")
      (node (ref "IC27") (pin "19") (pinfunction "B0+_19") (pintype "bidirectional"))
    )
    (net (code "67") (name "/EEM_IO.LVDS_P1") (class "Default")
      (node (ref "IC27") (pin "17") (pinfunction "B1+_17") (pintype "bidirectional"))
    )
    (net (code "68") (name "/EEM_IO.LVDS_P2") (class "Default")
      (node (ref "IC28") (pin "19") (pinfunction "B0+_19") (pintype "bidirectional"))
    )
    (net (code "69") (name "/EEM_IO.LVDS_P3") (class "Default")
      (node (ref "IC28") (pin "17") (pinfunction "B1+_17") (pintype "bidirectional"))
    )
    (net (code "70") (name "/EEM_IO.LVDS_P4") (class "Default")
      (node (ref "IC29") (pin "19") (pinfunction "B0+_19") (pintype "bidirectional"))
    )
    (net (code "71") (name "/EEM_IO.LVDS_P5") (class "Default")
      (node (ref "J8") (pin "17") (pinfunction "17_17") (pintype "bidirectional"))
      (node (ref "R150") (pin "2") (pinfunction "2_2") (pintype "passive"))
    )
    (net (code "72") (name "/EEM_IO.LVDS_P6") (class "Default")
      (node (ref "J8") (pin "20") (pinfunction "20_20") (pintype "bidirectional"))
      (node (ref "R151") (pin "2") (pinfunction "2_2") (pintype "passive"))
    )
    (net (code "73") (name "/EEM_IO.LVDS_P7") (class "Default")
      (node (ref "J8") (pin "23") (pinfunction "23_23") (pintype "bidirectional"))
      (node (ref "R152") (pin "2") (pinfunction "2_2") (pintype "passive"))
    )
    (net (code "74") (name "/EEM_IO.LVDS_P8") (class "Default")
      (node (ref "J9") (pin "2") (pinfunction "2_2") (pintype "bidirectional"))
      (node (ref "R153") (pin "2") (pinfunction "2_2") (pintype "passive"))
    )
    (net (code "75") (name "/EEM_IO.LVDS_P9") (class "Default")
      (node (ref "J9") (pin "5") (pinfunction "5_5") (pintype "bidirectional"))
      (node (ref "R154") (pin "2") (pinfunction "2_2") (pintype "passive"))
    )
    (net (code "76") (name "/EEM_IO.LVDS_P10") (class "Default")
      (node (ref "J9") (pin "8") (pinfunction "8_8") (pintype "bidirectional"))
      (node (ref "R155") (pin "2") (pinfunction "2_2") (pintype "passive"))
    )
    (net (code "77") (name "/EEM_IO.LVDS_P11") (class "Default")
      (node (ref "J9") (pin "11") (pinfunction "11_11") (pintype "bidirectional"))
      (node (ref "R156") (pin "2") (pinfunction "2_2") (pintype "passive"))
    )
    (net (code "78") (name "/EEM_IO.LVDS_P12") (class "Default")
      (node (ref "J9") (pin "14") (pinfunction "14_14") (pintype "bidirectional"))
      (node (ref "R157") (pin "2") (pinfunction "2_2") (pintype "passive"))
    )
    (net (code "79") (name "/EEM_IO.LVDS_P13") (class "Default")
      (node (ref "J9") (pin "17") (pinfunction "17_17") (pintype "bidirectional"))
      (node (ref "R158") (pin "2") (pinfunction "2_2") (pintype "passive"))
    )
    (net (code "80") (name "/EEM_IO.LVDS_P14") (class "Default")
      (node (ref "J9") (pin "20") (pinfunction "20_20") (pintype "bidirectional"))
      (node (ref "R159") (pin "2") (pinfunction "2_2") (pintype "passive"))
    )
    (net (code "81") (name "/EEM_IO.LVDS_P15") (class "Default")
      (node (ref "J9") (pin "23") (pinfunction "23_23") (pintype "bidirectional"))
      (node (ref "R143") (pin "1") (pinfunction "1_1") (pintype "passive"))
    )
    (net (code "83") (name "/I2C_SCL1") (class "Default")
      (node (ref "D8") (pin "6") (pinfunction "C_6") (pintype "passive"))
      (node (ref "IC26") (pin "6") (pinfunction "SCL_6") (pintype "input"))
      (node (ref "IC43") (pin "6") (pinfunction "SCL_6") (pintype "input"))
      (node (ref "J9") (pin "27") (pinfunction "27_27") (pintype "bidirectional"))
    )
    (net (code "84") (name "/I2C_SDA1") (class "Default")
      (node (ref "D8") (pin "4") (pinfunction "C_4") (pintype "passive"))
      (node (ref "IC26") (pin "5") (pinfunction "SDA_5") (pintype "bidirectional"))
      (node (ref "IC43") (pin "5") (pinfunction "SDA_5") (pintype "bidirectional"))
      (node (ref "J9") (pin "26") (pinfunction "26_26") (pintype "bidirectional"))
    )
    (net (code "85") (name "/LVDS_DUAL_N0") (class "Default")
      (node (ref "IC27") (pin "4") (pinfunction "A0-_4") (pintype "bidirectional"))
      (node (ref "J8") (pin "3") (pinfunction "3_3") (pintype "bidirectional"))
      (node (ref "R161") (pin "2") (pinfunction "2_2") (pintype "passive"))
    )
    (net (code "86") (name "/LVDS_DUAL_N1") (class "Default")
      (node (ref "IC27") (pin "8") (pinfunction "A1-_8") (pintype "bidirectional"))
      (node (ref "J8") (pin "6") (pinfunction "6_6") (pintype "bidirectional"))
      (node (ref "R162") (pin "2") (pinfunction "2_2") (pintype "passive"))
    )
    (net (code "87") (name "/LVDS_DUAL_N2") (class "Default")
      (node (ref "IC28") (pin "4") (pinfunction "A0-_4") (pintype "bidirectional"))
      (node (ref "J8") (pin "9") (pinfunction "9_9") (pintype "bidirectional"))
      (node (ref "R163") (pin "2") (pinfunction "2_2") (pintype "passive"))
    )
    (net (code "88") (name "/LVDS_DUAL_N3") (class "Default")
      (node (ref "IC28") (pin "8") (pinfunction "A1-_8") (pintype "bidirectional"))
      (node (ref "J8") (pin "12") (pinfunction "12_12") (pintype "bidirectional"))
      (node (ref "R164") (pin "2") (pinfunction "2_2") (pintype "passive"))
    )
    (net (code "89") (name "/LVDS_DUAL_N4") (class "Default")
      (node (ref "IC29") (pin "4") (pinfunction "A0-_4") (pintype "bidirectional"))
      (node (ref "J8") (pin "15") (pinfunction "15_15") (pintype "bidirectional"))
      (node (ref "R167") (pin "2") (pinfunction "2_2") (pintype "passive"))
    )
    (net (code "91") (name "/LVDS_DUAL_P0") (class "Default")
      (node (ref "IC27") (pin "3") (pinfunction "A0+_3") (pintype "bidirectional"))
      (node (ref "J8") (pin "2") (pinfunction "2_2") (pintype "bidirectional"))
      (node (ref "R145") (pin "2") (pinfunction "2_2") (pintype "passive"))
    )
    (net (code "92") (name "/LVDS_DUAL_P1") (class "Default")
      (node (ref "IC27") (pin "7") (pinfunction "A1+_7") (pintype "bidirectional"))
      (node (ref "J8") (pin "5") (pinfunction "5_5") (pintype "bidirectional"))
      (node (ref "R146") (pin "2") (pinfunction "2_2") (pintype "passive"))
    )
    (net (code "93") (name "/LVDS_DUAL_P2") (class "Default")
      (node (ref "IC28") (pin "3") (pinfunction "A0+_3") (pintype "bidirectional"))
      (node (ref "J8") (pin "8") (pinfunction "8_8") (pintype "bidirectional"))
      (node (ref "R147") (pin "2") (pinfunction "2_2") (pintype "passive"))
    )
    (net (code "94") (name "/LVDS_DUAL_P3") (class "Default")
      (node (ref "IC28") (pin "7") (pinfunction "A1+_7") (pintype "bidirectional"))
      (node (ref "J8") (pin "11") (pinfunction "11_11") (pintype "bidirectional"))
      (node (ref "R148") (pin "2") (pinfunction "2_2") (pintype "passive"))
    )
    (net (code "95") (name "/LVDS_DUAL_P4") (class "Default")
      (node (ref "IC29") (pin "3") (pinfunction "A0+_3") (pintype "bidirectional"))
      (node (ref "J8") (pin "14") (pinfunction "14_14") (pintype "bidirectional"))
      (node (ref "R149") (pin "2") (pinfunction "2_2") (pintype "passive"))
    )
    (net (code "97") (name "/LVDS_JTAG_TCK_N") (class "Default")
      (node (ref "IC29") (pin "14") (pinfunction "C0-_14") (pintype "bidirectional"))
      (node (ref "IC30") (pin "8") (pinfunction "IN4-_8") (pintype "input"))
    )
    (net (code "98") (name "/LVDS_JTAG_TCK_P") (class "Default")
      (node (ref "IC29") (pin "15") (pinfunction "C0+_15") (pintype "bidirectional"))
      (node (ref "IC30") (pin "7") (pinfunction "IN4+_7") (pintype "input"))
    )
    (net (code "99") (name "/LVDS_JTAG_TDI_N") (class "Default")
      (node (ref "IC27") (pin "12") (pinfunction "C1-_12") (pintype "bidirectional"))
      (node (ref "IC30") (pin "1") (pinfunction "IN1-_1") (pintype "input"))
    )
    (net (code "100") (name "/LVDS_JTAG_TDI_P") (class "Default")
      (node (ref "IC27") (pin "13") (pinfunction "C1+_13") (pintype "bidirectional"))
      (node (ref "IC30") (pin "2") (pinfunction "IN1+_2") (pintype "input"))
    )
    (net (code "101") (name "/LVDS_JTAG_TDO_N") (class "Default")
      (node (ref "IC27") (pin "14") (pinfunction "C0-_14") (pintype "bidirectional"))
      (node (ref "IC31") (pin "8") (pinfunction "DOUT-_8") (pintype "output"))
    )
    (net (code "102") (name "/LVDS_JTAG_TDO_P") (class "Default")
      (node (ref "IC27") (pin "15") (pinfunction "C0+_15") (pintype "bidirectional"))
      (node (ref "IC31") (pin "7") (pinfunction "DOUT+_7") (pintype "output"))
    )
    (net (code "103") (name "/LVDS_JTAG_TMS_N") (class "Default")
      (node (ref "IC28") (pin "14") (pinfunction "C0-_14") (pintype "bidirectional"))
      (node (ref "IC30") (pin "5") (pinfunction "IN3-_5") (pintype "input"))
    )
    (net (code "104") (name "/LVDS_JTAG_TMS_P") (class "Default")
      (node (ref "IC28") (pin "15") (pinfunction "C0+_15") (pintype "bidirectional"))
      (node (ref "IC30") (pin "6") (pinfunction "IN3+_6") (pintype "input"))
    )
    (net (code "105") (name "/LVDS_JTAG_TRSTn_N") (class "Default")
      (node (ref "IC28") (pin "12") (pinfunction "C1-_12") (pintype "bidirectional"))
      (node (ref "IC30") (pin "4") (pinfunction "IN2-_4") (pintype "input"))
    )
    (net (code "106") (name "/LVDS_JTAG_TRSTn_P") (class "Default")
      (node (ref "IC28") (pin "13") (pinfunction "C1+_13") (pintype "bidirectional"))
      (node (ref "IC30") (pin "3") (pinfunction "IN2+_3") (pintype "input"))
    )
    (net (code "107") (name "/SERVMOD_3V3") (class "Default")
      (node (ref "IC27") (pin "9") (pinfunction "SEL_9") (pintype "input"))
      (node (ref "IC28") (pin "9") (pinfunction "SEL_9") (pintype "input"))
      (node (ref "IC29") (pin "9") (pinfunction "SEL_9") (pintype "input"))
      (node (ref "IC30") (pin "16") (pinfunction "EN_16") (pintype "input"))
      (node (ref "IC40") (pin "13") (pinfunction "E_13") (pintype "input"))
      (node (ref "IC40") (pin "5") (pinfunction "E_5") (pintype "input"))
    )
    (net (code "108") (name "/Switch_I2C.SCL") (class "Default")
      (node (ref "IC40") (pin "2") (pinfunction "Z_2") (pintype "bidirectional"))
      (node (ref "R77") (pin "2") (pinfunction "2_2") (pintype "passive"))
    )
    (net (code "109") (name "/Switch_I2C.SDA") (class "Default")
      (node (ref "IC40") (pin "3") (pinfunction "Z_3") (pintype "bidirectional"))
      (node (ref "R3") (pin "2") (pinfunction "2_2") (pintype "passive"))
    )
    (net (code "113") (name "GND") (class "Default")
      (node (ref "C219") (pin "1") (pinfunction "1_1") (pintype "passive"))
      (node (ref "C220") (pin "1") (pinfunction "1_1") (pintype "passive"))
      (node (ref "C221") (pin "1") (pinfunction "1_1") (pintype "passive"))
      (node (ref "C222") (pin "1") (pinfunction "1_1") (pintype "passive"))
      (node (ref "C223") (pin "1") (pinfunction "1_1") (pintype "passive"))
      (node (ref "C224") (pin "1") (pinfunction "1_1") (pintype "passive"))
      (node (ref "C225") (pin "1") (pinfunction "1_1") (pintype "passive"))
      (node (ref "C226") (pin "1") (pinfunction "1_1") (pintype "passive"))
      (node (ref "C298") (pin "1") (pinfunction "1_1") (pintype "passive"))
      (node (ref "C306") (pin "1") (pinfunction "1_1") (pintype "passive"))
      (node (ref "C307") (pin "1") (pinfunction "1_1") (pintype "passive"))
      (node (ref "D8") (pin "2") (pinfunction "A_2") (pintype "passive"))
      (node (ref "IC25") (pin "1") (pinfunction "A0_1") (pintype "input"))
      (node (ref "IC25") (pin "2") (pinfunction "A1_2") (pintype "input"))
      (node (ref "IC25") (pin "3") (pinfunction "A2_3") (pintype "input"))
      (node (ref "IC25") (pin "4") (pinfunction "VSS_4") (pintype "power_in"))
      (node (ref "IC26") (pin "1") (pinfunction "A0_1") (pintype "input"))
      (node (ref "IC26") (pin "2") (pinfunction "A1_2") (pintype "input"))
      (node (ref "IC26") (pin "3") (pinfunction "A2_3") (pintype "input"))
      (node (ref "IC26") (pin "4") (pinfunction "VSS_4") (pintype "power_in"))
      (node (ref "IC27") (pin "11") (pinfunction "GND_11") (pintype "power_in"))
      (node (ref "IC27") (pin "20") (pinfunction "GND_20") (pintype "power_in"))
      (node (ref "IC27") (pin "21") (pinfunction "EP_21") (pintype "power_in"))
      (node (ref "IC27") (pin "5") (pinfunction "GND_5") (pintype "power_in"))
      (node (ref "IC28") (pin "11") (pinfunction "GND_11") (pintype "power_in"))
      (node (ref "IC28") (pin "20") (pinfunction "GND_20") (pintype "power_in"))
      (node (ref "IC28") (pin "21") (pinfunction "EP_21") (pintype "power_in"))
      (node (ref "IC28") (pin "5") (pinfunction "GND_5") (pintype "power_in"))
      (node (ref "IC29") (pin "11") (pinfunction "GND_11") (pintype "power_in"))
      (node (ref "IC29") (pin "20") (pinfunction "GND_20") (pintype "power_in"))
      (node (ref "IC29") (pin "21") (pinfunction "EP_21") (pintype "power_in"))
      (node (ref "IC29") (pin "5") (pinfunction "GND_5") (pintype "power_in"))
      (node (ref "IC30") (pin "12") (pinfunction "GND_12") (pintype "power_in"))
      (node (ref "IC30") (pin "9") (pinfunction "~{EN}_9") (pintype "input"))
      (node (ref "IC31") (pin "4") (pinfunction "GND_4") (pintype "power_in"))
      (node (ref "IC40") (pin "10") (pinfunction "Z_10") (pintype "bidirectional"))
      (node (ref "IC40") (pin "11") (pinfunction "Y_11") (pintype "bidirectional"))
      (node (ref "IC40") (pin "12") (pinfunction "E_12") (pintype "input"))
      (node (ref "IC40") (pin "6") (pinfunction "E_6") (pintype "input"))
      (node (ref "IC40") (pin "7") (pinfunction "GND_7") (pintype "power_in"))
      (node (ref "IC40") (pin "8") (pinfunction "Y_8") (pintype "bidirectional"))
      (node (ref "IC40") (pin "9") (pinfunction "Z_9") (pintype "bidirectional"))
      (node (ref "IC42") (pin "4") (pinfunction "VSS_4") (pintype "passive"))
      (node (ref "IC43") (pin "4") (pinfunction "VSS_4") (pintype "passive"))
      (node (ref "J8") (pin "1") (pinfunction "1_1") (pintype "bidirectional"))
      (node (ref "J8") (pin "10") (pinfunction "10_10") (pintype "bidirectional"))
      (node (ref "J8") (pin "13") (pinfunction "13_13") (pintype "bidirectional"))
      (node (ref "J8") (pin "16") (pinfunction "16_16") (pintype "bidirectional"))
      (node (ref "J8") (pin "19") (pinfunction "19_19") (pintype "bidirectional"))
      (node (ref "J8") (pin "22") (pinfunction "22_22") (pintype "bidirectional"))
      (node (ref "J8") (pin "25") (pinfunction "25_25") (pintype "bidirectional"))
      (node (ref "J8") (pin "4") (pinfunction "4_4") (pintype "bidirectional"))
      (node (ref "J8") (pin "7") (pinfunction "7_7") (pintype "bidirectional"))
      (node (ref "J9") (pin "1") (pinfunction "1_1") (pintype "bidirectional"))
      (node (ref "J9") (pin "10") (pinfunction "10_10") (pintype "bidirectional"))
      (node (ref "J9") (pin "13") (pinfunction "13_13") (pintype "bidirectional"))
      (node (ref "J9") (pin "16") (pinfunction "16_16") (pintype "bidirectional"))
      (node (ref "J9") (pin "19") (pinfunction "19_19") (pintype "bidirectional"))
      (node (ref "J9") (pin "22") (pinfunction "22_22") (pintype "bidirectional"))
      (node (ref "J9") (pin "25") (pinfunction "25_25") (pintype "bidirectional"))
      (node (ref "J9") (pin "4") (pinfunction "4_4") (pintype "bidirectional"))
      (node (ref "J9") (pin "7") (pinfunction "7_7") (pintype "bidirectional"))
      (node (ref "R181") (pin "2") (pinfunction "2_2") (pintype "passive"))
      (node (ref "R182") (pin "2") (pinfunction "2_2") (pintype "passive"))
      (node (ref "R183") (pin "2") (pinfunction "2_2") (pintype "passive"))
    )
    (net (code "114") (name "Net-(IC27-OEn)") (class "Default")
      (node (ref "IC27") (pin "2") (pinfunction "OEn_2") (pintype "input"))
      (node (ref "R181") (pin "1") (pinfunction "1_1") (pintype "passive"))
    )
    (net (code "115") (name "Net-(IC28-OEn)") (class "Default")
      (node (ref "IC28") (pin "2") (pinfunction "OEn_2") (pintype "input"))
      (node (ref "R182") (pin "1") (pinfunction "1_1") (pintype "passive"))
    )
    (net (code "116") (name "Net-(IC29-OEn)") (class "Default")
      (node (ref "IC29") (pin "2") (pinfunction "OEn_2") (pintype "input"))
      (node (ref "R183") (pin "1") (pinfunction "1_1") (pintype "passive"))
    )
    (net (code "117") (name "P3V3") (class "Default")
      (node (ref "C221") (pin "2") (pinfunction "2_2") (pintype "passive"))
      (node (ref "C222") (pin "2") (pinfunction "2_2") (pintype "passive"))
      (node (ref "C223") (pin "2") (pinfunction "2_2") (pintype "passive"))
      (node (ref "C224") (pin "2") (pinfunction "2_2") (pintype "passive"))
      (node (ref "C225") (pin "2") (pinfunction "2_2") (pintype "passive"))
      (node (ref "C226") (pin "2") (pinfunction "2_2") (pintype "passive"))
      (node (ref "C298") (pin "2") (pinfunction "2_2") (pintype "passive"))
      (node (ref "IC27") (pin "1") (pinfunction "RSVD1_1") (pintype "power_in"))
      (node (ref "IC27") (pin "10") (pinfunction "RSVD2_10") (pintype "power_in"))
      (node (ref "IC27") (pin "6") (pinfunction "VDD_6") (pintype "power_in"))
      (node (ref "IC28") (pin "1") (pinfunction "RSVD1_1") (pintype "power_in"))
      (node (ref "IC28") (pin "10") (pinfunction "RSVD2_10") (pintype "power_in"))
      (node (ref "IC28") (pin "6") (pinfunction "VDD_6") (pintype "power_in"))
      (node (ref "IC29") (pin "1") (pinfunction "RSVD1_1") (pintype "power_in"))
      (node (ref "IC29") (pin "10") (pinfunction "RSVD2_10") (pintype "power_in"))
      (node (ref "IC29") (pin "6") (pinfunction "VDD_6") (pintype "power_in"))
      (node (ref "IC30") (pin "13") (pinfunction "VCC_13") (pintype "power_in"))
      (node (ref "IC31") (pin "1") (pinfunction "VCC_1") (pintype "power_in"))
      (node (ref "IC40") (pin "14") (pinfunction "VCC_14") (pintype "power_in"))
    )
    (net (code "118") (name "P3V3_MP") (class "Default")
      (node (ref "C219") (pin "2") (pinfunction "2_2") (pintype "passive"))
      (node (ref "C306") (pin "2") (pinfunction "2_2") (pintype "passive"))
      (node (ref "IC25") (pin "8") (pinfunction "VCC_8") (pintype "power_in"))
      (node (ref "IC42") (pin "8") (pinfunction "VCC_8") (pintype "passive"))
      (node (ref "J8") (pin "30") (pinfunction "30_30") (pintype "bidirectional"))
    )
    (net (code "119") (name "P3V3_MP2") (class "Default")
      (node (ref "C220") (pin "2") (pinfunction "2_2") (pintype "passive"))
      (node (ref "C307") (pin "2") (pinfunction "2_2") (pintype "passive"))
      (node (ref "IC26") (pin "8") (pinfunction "VCC_8") (pintype "power_in"))
      (node (ref "IC43") (pin "8") (pinfunction "VCC_8") (pintype "passive"))
      (node (ref "J9") (pin "30") (pinfunction "30_30") (pintype "bidirectional"))
    )
    (net (code "120") (name "P12V0") (class "Default")
      (node (ref "J8") (pin "28") (pinfunction "28_28") (pintype "bidirectional"))
      (node (ref "J8") (pin "29") (pinfunction "29_29") (pintype "bidirectional"))
      (node (ref "J9") (pin "28") (pinfunction "28_28") (pintype "bidirectional"))
      (node (ref "J9") (pin "29") (pinfunction "29_29") (pintype "bidirectional"))
    )
    (net (code "121") (name "unconnected-(D8D-C-Pad5)") (class "Default")
      (node (ref "D8") (pin "5") (pinfunction "C_5") (pintype "passive+no_connect"))
    )
    (net (code "122") (name "unconnected-(IC25-NC-Pad7)") (class "Default")
      (node (ref "IC25") (pin "7") (pinfunction "NC_7") (pintype "passive+no_connect"))
    )
    (net (code "123") (name "unconnected-(IC26-NC-Pad7)") (class "Default")
      (node (ref "IC26") (pin "7") (pinfunction "NC_7") (pintype "passive+no_connect"))
    )
    (net (code "124") (name "unconnected-(IC29-A1+-Pad7)") (class "Default")
      (node (ref "IC29") (pin "7") (pinfunction "A1+_7") (pintype "bidirectional"))
    )
    (net (code "125") (name "unconnected-(IC29-A1--Pad8)") (class "Default")
      (node (ref "IC29") (pin "8") (pinfunction "A1-_8") (pintype "bidirectional"))
    )
    (net (code "126") (name "unconnected-(IC29-B1+-Pad17)") (class "Default")
      (node (ref "IC29") (pin "17") (pinfunction "B1+_17") (pintype "bidirectional+no_connect"))
    )
    (net (code "127") (name "unconnected-(IC29-B1--Pad16)") (class "Default")
      (node (ref "IC29") (pin "16") (pinfunction "B1-_16") (pintype "bidirectional+no_connect"))
    )
    (net (code "128") (name "unconnected-(IC29-C1+-Pad13)") (class "Default")
      (node (ref "IC29") (pin "13") (pinfunction "C1+_13") (pintype "bidirectional"))
    )
    (net (code "129") (name "unconnected-(IC29-C1--Pad12)") (class "Default")
      (node (ref "IC29") (pin "12") (pinfunction "C1-_12") (pintype "bidirectional"))
    )
    (net (code "130") (name "unconnected-(IC31-NC-Pad3)") (class "Default")
      (node (ref "IC31") (pin "3") (pinfunction "NC_3") (pintype "passive"))
    )
    (net (code "131") (name "unconnected-(IC31-NC-Pad5)") (class "Default")
      (node (ref "IC31") (pin "5") (pinfunction "NC_5") (pintype "passive"))
    )
    (net (code "132") (name "unconnected-(IC31-NC-Pad6)") (class "Default")
      (node (ref "IC31") (pin "6") (pinfunction "NC_6") (pintype "passive"))
    )
    (net (code "133") (name "unconnected-(IC42-A0_(NC)-Pad1)") (class "Default")
      (node (ref "IC42") (pin "1") (pinfunction "A0_(NC)_1") (pintype "input+no_connect"))
    )
    (net (code "134") (name "unconnected-(IC42-A1_(NC)-Pad2)") (class "Default")
      (node (ref "IC42") (pin "2") (pinfunction "A1_(NC)_2") (pintype "input+no_connect"))
    )
    (net (code "135") (name "unconnected-(IC42-A2_(NC)-Pad3)") (class "Default")
      (node (ref "IC42") (pin "3") (pinfunction "A2_(NC)_3") (pintype "input+no_connect"))
    )
    (net (code "136") (name "unconnected-(IC42-NC-Pad7)") (class "Default")
      (node (ref "IC42") (pin "7") (pinfunction "NC_7") (pintype "passive+no_connect"))
    )
    (net (code "137") (name "unconnected-(IC43-A0_(NC)-Pad1)") (class "Default")
      (node (ref "IC43") (pin "1") (pinfunction "A0_(NC)_1") (pintype "input+no_connect"))
    )
    (net (code "138") (name "unconnected-(IC43-A1_(NC)-Pad2)") (class "Default")
      (node (ref "IC43") (pin "2") (pinfunction "A1_(NC)_2") (pintype "input+no_connect"))
    )
    (net (code "139") (name "unconnected-(IC43-A2_(NC)-Pad3)") (class "Default")
      (node (ref "IC43") (pin "3") (pinfunction "A2_(NC)_3") (pintype "input+no_connect"))
    )
    (net (code "140") (name "unconnected-(IC43-NC-Pad7)") (class "Default")
      (node (ref "IC43") (pin "7") (pinfunction "NC_7") (pintype "passive+no_connect"))
    )
  )
)
